# Power.net
KiCad netlist of a schematic drawn in Altium Designer
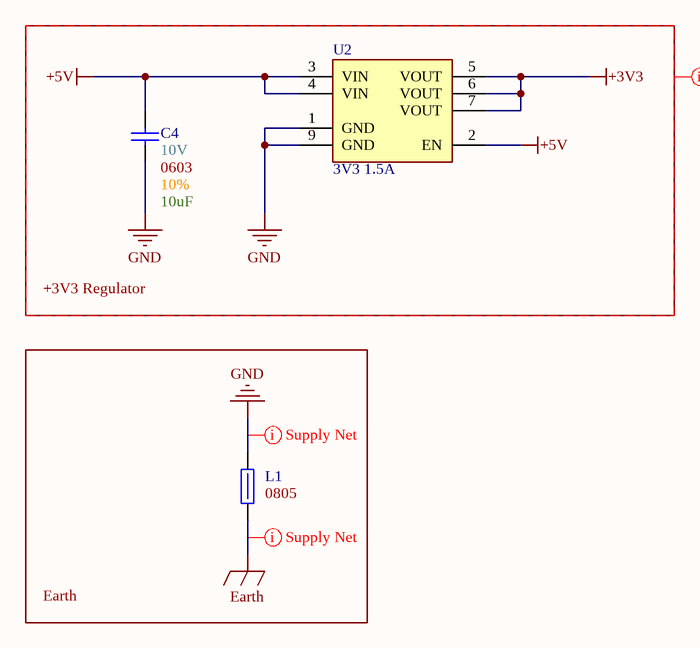
[diagram p0: Power.SchDoc]

(export (version "E")
  (design (tool "Eeschema 10.0.6"))
  (components
    (comp (ref "C4")
      (value "[Cap] 0603 10uF 10% 10V")
      (footprint "[Cap] SMD 0603")
      (description "CL10A106KP8NNNC")
      (fields
        (field (name "MAX VOLTAGE") "10V")
        (field (name "SIZE PACKAGE") "0603")
        (field (name "TOLERANCE") "10%")
        (field (name "CAPACITANCE") "10uF")
      )
      (libsource (lib "Capacitors") (part "[Cap] 0603 10uF 10% 10V"))
    )
    (comp (ref "L1")
      (value "652-MH2029-300Y")
      (footprint "[Ferrite] SMD 0805")
      (fields (field (name "SIZE PACKAGE") "0805"))
      (libsource (lib "Ferrite Beads") (part "[Ferrite] SMD 0805 3A 30ohm"))
    )
    (comp (ref "U2")
      (value "3V3 1.5A")
      (footprint "[Linear] 3V3 1.5A")
      (description "AP7362A-33SP-13")
      (libsource (lib "Voltage Regulators") (part "[Linear] 3V3 1.5A"))
    )
  )
  (nets
    (net (code "1") (name "+3V3") (class "Default")
      (node (ref "U2") (pin "5") (pinfunction "VOUT_5") (pintype "passive"))
      (node (ref "U2") (pin "6") (pinfunction "VOUT_6") (pintype "passive"))
      (node (ref "U2") (pin "7") (pinfunction "VOUT_7") (pintype "passive"))
    )
    (net (code "2") (name "+5V") (class "Default")
      (node (ref "C4") (pin "2") (pinfunction "2_2") (pintype "passive"))
      (node (ref "U2") (pin "2") (pinfunction "EN_2") (pintype "passive"))
      (node (ref "U2") (pin "3") (pinfunction "VIN_3") (pintype "passive"))
      (node (ref "U2") (pin "4") (pinfunction "VIN_4") (pintype "passive"))
    )
    (net (code "3") (name "Earth") (class "Default")
      (node (ref "L1") (pin "1") (pinfunction "1_1") (pintype "passive"))
    )
    (net (code "4") (name "GND") (class "Default")
      (node (ref "C4") (pin "1") (pinfunction "1_1") (pintype "passive"))
      (node (ref "L1") (pin "2") (pinfunction "2_2") (pintype "passive"))
      (node (ref "U2") (pin "1") (pinfunction "GND_1") (pintype "passive"))
      (node (ref "U2") (pin "9") (pinfunction "GND_9") (pintype "passive"))
    )
  )
)
